# RevA.net
KiCad netlist of a schematic drawn in EAGLE
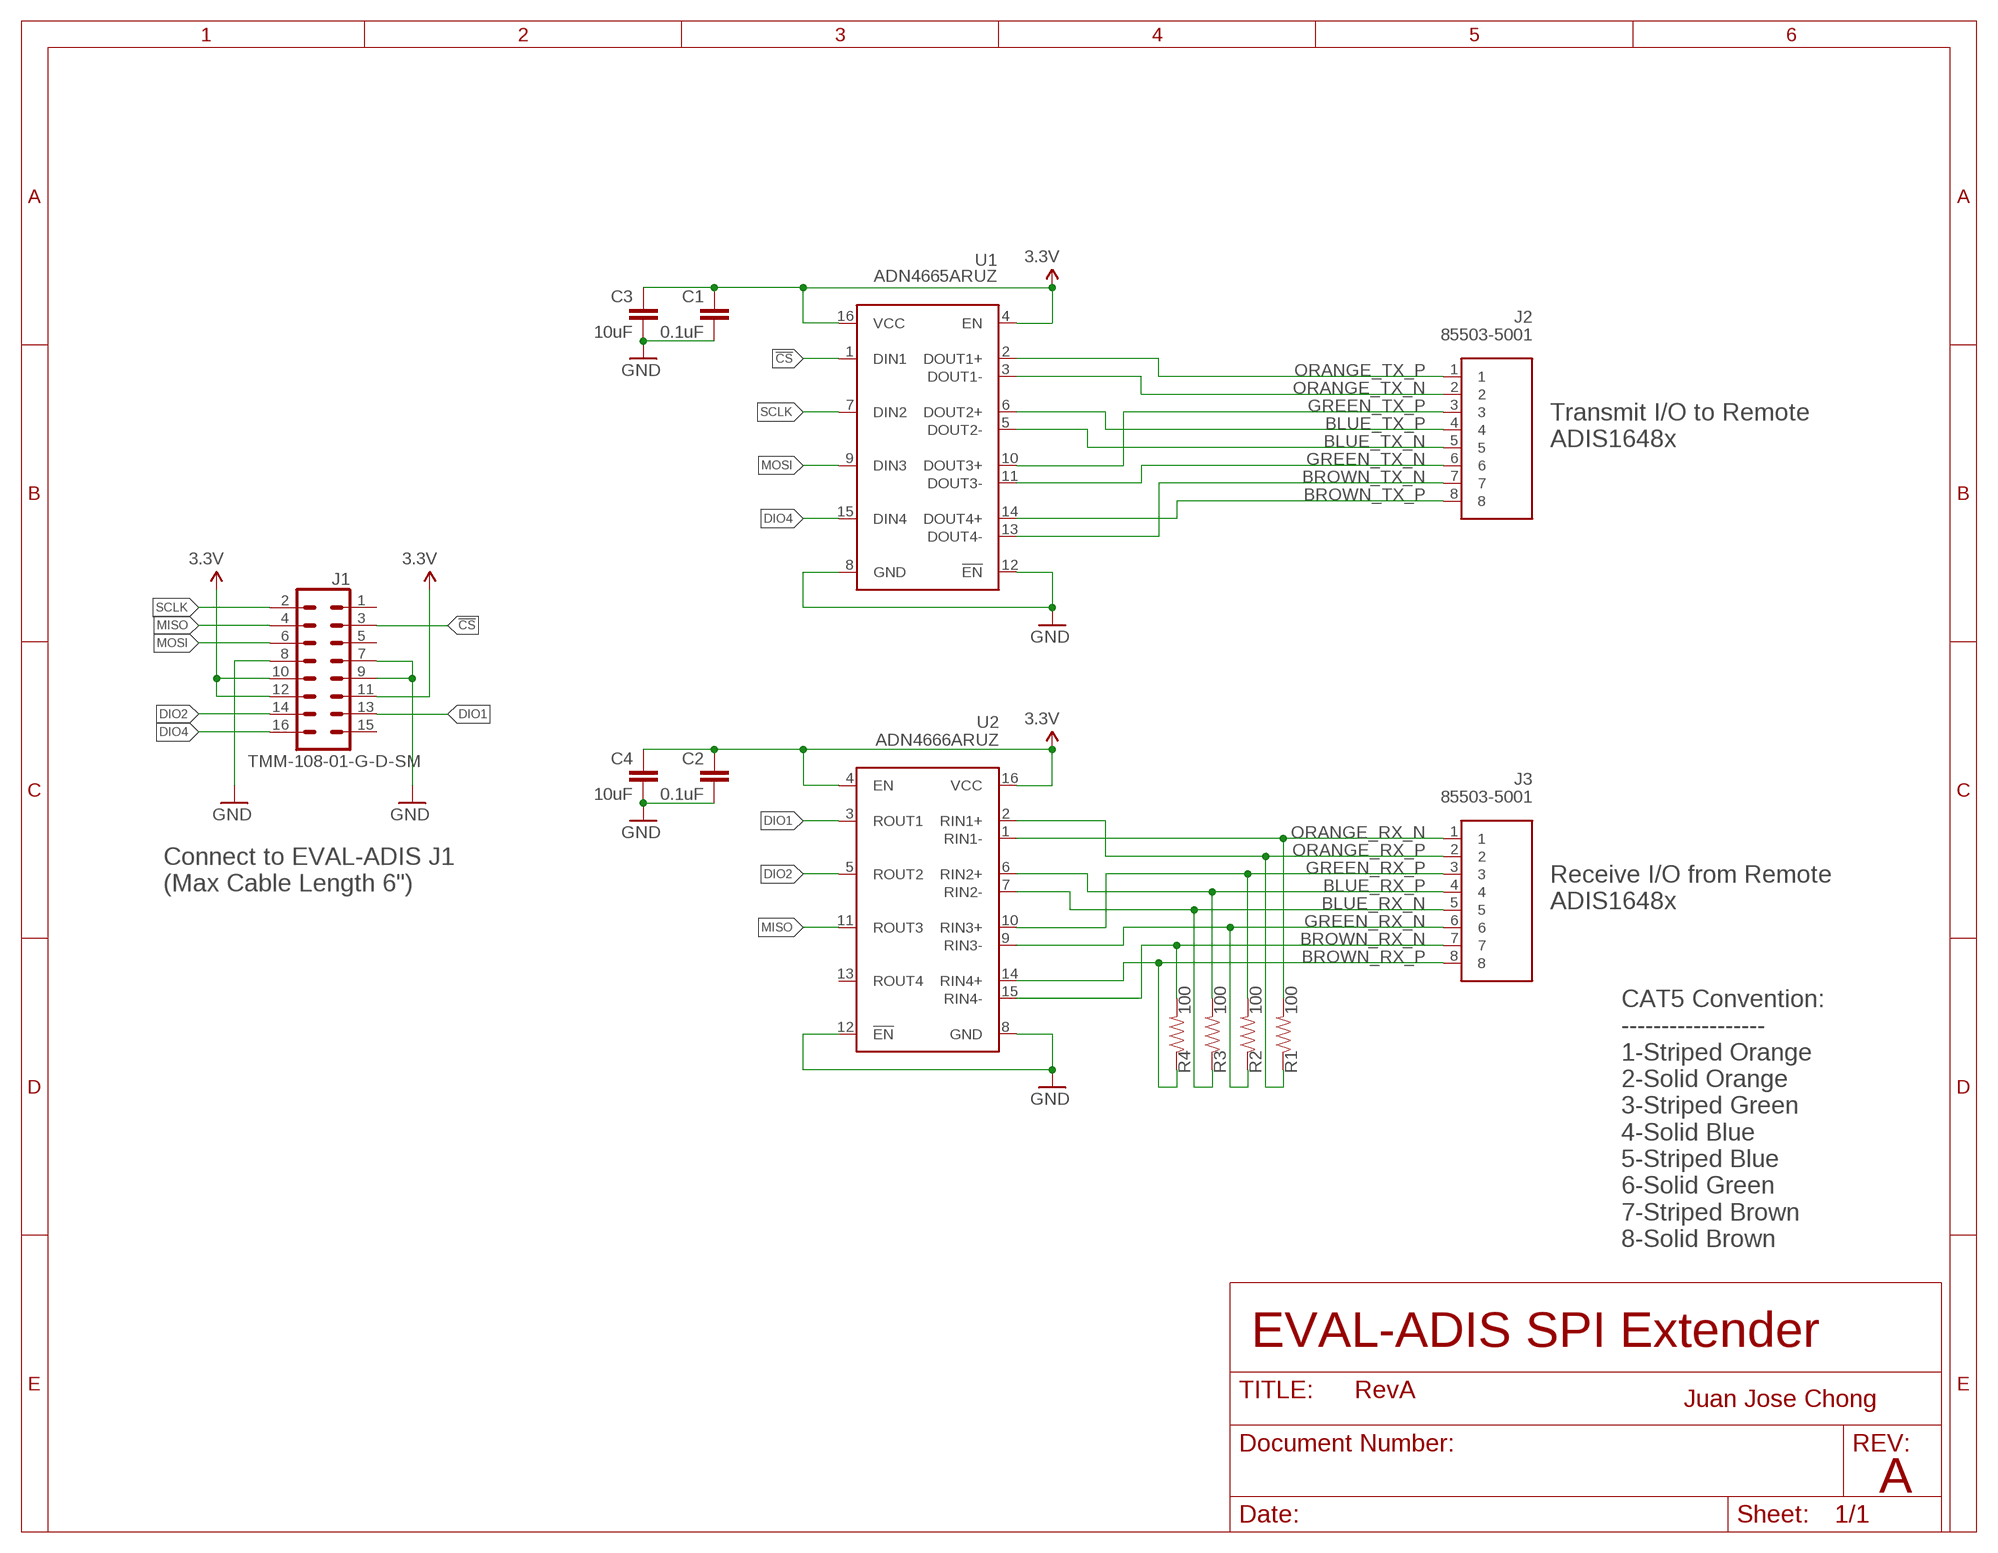
[diagram p0: schematic, sheet 1]

(export (version "E")
  (design (tool "Eeschema 10.0.6"))
  (components
    (comp (ref "C1")
      (value "0.1uF")
      (footprint "eagle-import:0805")
      (fields (field (name "PARTNO") "CL10B104KB8NNNC"))
      (libsource (lib "eagle-import") (part "CAP0805"))
    )
    (comp (ref "C2")
      (value "0.1uF")
      (footprint "eagle-import:0805")
      (fields (field (name "PARTNO") "CL10B104KB8NNNC"))
      (libsource (lib "eagle-import") (part "CAP0805"))
    )
    (comp (ref "C3")
      (value "10uF")
      (footprint "eagle-import:1206")
      (fields (field (name "PARTNO") "F931C106MAA"))
      (libsource (lib "eagle-import") (part "CAP1206"))
    )
    (comp (ref "C4")
      (value "10uF")
      (footprint "eagle-import:1206")
      (fields (field (name "PARTNO") "F931C106MAA"))
      (libsource (lib "eagle-import") (part "CAP1206"))
    )
    (comp (ref "J1")
      (value "TMM-108-01-G-D-SM")
      (footprint "eagle-import:TMM-108-XX-X-D")
      (libsource (lib "eagle-import") (part "TMM-108-XX-X-D"))
    )
    (comp (ref "J2")
      (value "85503-5001")
      (footprint "eagle-import:85503-5001")
      (fields (field (name "PARTNO") "855035001"))
      (libsource (lib "eagle-import") (part "85503-5001"))
    )
    (comp (ref "J3")
      (value "85503-5001")
      (footprint "eagle-import:85503-5001")
      (fields (field (name "PARTNO") "855035001"))
      (libsource (lib "eagle-import") (part "85503-5001"))
    )
    (comp (ref "R1")
      (value "100")
      (footprint "eagle-import:0603-RES")
      (fields (field (name "PARTNO") "ERJ-3EKF1000V"))
      (libsource (lib "eagle-import") (part "RESISTOR0603-RES"))
    )
    (comp (ref "R2")
      (value "100")
      (footprint "eagle-import:0603-RES")
      (fields (field (name "PARTNO") "ERJ-3EKF1000V"))
      (libsource (lib "eagle-import") (part "RESISTOR0603-RES"))
    )
    (comp (ref "R3")
      (value "100")
      (footprint "eagle-import:0603-RES")
      (fields (field (name "PARTNO") "ERJ-3EKF1000V"))
      (libsource (lib "eagle-import") (part "RESISTOR0603-RES"))
    )
    (comp (ref "R4")
      (value "100")
      (footprint "eagle-import:0603-RES")
      (fields (field (name "PARTNO") "ERJ-3EKF1000V"))
      (libsource (lib "eagle-import") (part "RESISTOR0603-RES"))
    )
    (comp (ref "U1")
      (value "ADN4665ARUZ")
      (footprint "eagle-import:TSSOP-16")
      (libsource (lib "eagle-import") (part "ADN4665ARUZ"))
    )
    (comp (ref "U2")
      (value "ADN4666ARUZ")
      (footprint "eagle-import:TSSOP-16")
      (libsource (lib "eagle-import") (part "ADN4666ARUZ"))
    )
  )
  (nets
    (net (code "1") (name "/BLUE_RX_N") (class "Default")
      (node (ref "J3") (pin "5") (pinfunction "5_5") (pintype "bidirectional"))
      (node (ref "R3") (pin "1") (pinfunction "1_1") (pintype "passive"))
      (node (ref "U2") (pin "7") (pinfunction "RIN2-_7") (pintype "bidirectional"))
    )
    (net (code "2") (name "/BLUE_RX_P") (class "Default")
      (node (ref "J3") (pin "4") (pinfunction "4_4") (pintype "bidirectional"))
      (node (ref "R3") (pin "2") (pinfunction "2_2") (pintype "passive"))
      (node (ref "U2") (pin "6") (pinfunction "RIN2+_6") (pintype "bidirectional"))
    )
    (net (code "3") (name "/BLUE_TX_N") (class "Default")
      (node (ref "J2") (pin "5") (pinfunction "5_5") (pintype "bidirectional"))
      (node (ref "U1") (pin "5") (pinfunction "DOUT2-_5") (pintype "bidirectional"))
    )
    (net (code "4") (name "/BLUE_TX_P") (class "Default")
      (node (ref "J2") (pin "4") (pinfunction "4_4") (pintype "bidirectional"))
      (node (ref "U1") (pin "6") (pinfunction "DOUT2+_6") (pintype "bidirectional"))
    )
    (net (code "5") (name "/BROWN_RX_N") (class "Default")
      (node (ref "J3") (pin "7") (pinfunction "7_7") (pintype "bidirectional"))
      (node (ref "R4") (pin "2") (pinfunction "2_2") (pintype "passive"))
      (node (ref "U2") (pin "15") (pinfunction "RIN4-_15") (pintype "bidirectional"))
    )
    (net (code "6") (name "/BROWN_RX_P") (class "Default")
      (node (ref "J3") (pin "8") (pinfunction "8_8") (pintype "bidirectional"))
      (node (ref "R4") (pin "1") (pinfunction "1_1") (pintype "passive"))
      (node (ref "U2") (pin "14") (pinfunction "RIN4+_14") (pintype "bidirectional"))
    )
    (net (code "7") (name "/BROWN_TX_N") (class "Default")
      (node (ref "J2") (pin "7") (pinfunction "7_7") (pintype "bidirectional"))
      (node (ref "U1") (pin "13") (pinfunction "DOUT4-_13") (pintype "bidirectional"))
    )
    (net (code "8") (name "/BROWN_TX_P") (class "Default")
      (node (ref "J2") (pin "8") (pinfunction "8_8") (pintype "bidirectional"))
      (node (ref "U1") (pin "14") (pinfunction "DOUT4+_14") (pintype "bidirectional"))
    )
    (net (code "9") (name "/GREEN_RX_N") (class "Default")
      (node (ref "J3") (pin "6") (pinfunction "6_6") (pintype "bidirectional"))
      (node (ref "R2") (pin "1") (pinfunction "1_1") (pintype "passive"))
      (node (ref "U2") (pin "9") (pinfunction "RIN3-_9") (pintype "bidirectional"))
    )
    (net (code "10") (name "/GREEN_RX_P") (class "Default")
      (node (ref "J3") (pin "3") (pinfunction "3_3") (pintype "bidirectional"))
      (node (ref "R2") (pin "2") (pinfunction "2_2") (pintype "passive"))
      (node (ref "U2") (pin "10") (pinfunction "RIN3+_10") (pintype "bidirectional"))
    )
    (net (code "11") (name "/GREEN_TX_N") (class "Default")
      (node (ref "J2") (pin "6") (pinfunction "6_6") (pintype "bidirectional"))
      (node (ref "U1") (pin "11") (pinfunction "DOUT3-_11") (pintype "bidirectional"))
    )
    (net (code "12") (name "/GREEN_TX_P") (class "Default")
      (node (ref "J2") (pin "3") (pinfunction "3_3") (pintype "bidirectional"))
      (node (ref "U1") (pin "10") (pinfunction "DOUT3+_10") (pintype "bidirectional"))
    )
    (net (code "13") (name "/ORANGE_RX_N") (class "Default")
      (node (ref "J3") (pin "1") (pinfunction "1_1") (pintype "bidirectional"))
      (node (ref "R1") (pin "2") (pinfunction "2_2") (pintype "passive"))
      (node (ref "U2") (pin "1") (pinfunction "RIN1-_1") (pintype "bidirectional"))
    )
    (net (code "14") (name "/ORANGE_RX_P") (class "Default")
      (node (ref "J3") (pin "2") (pinfunction "2_2") (pintype "bidirectional"))
      (node (ref "R1") (pin "1") (pinfunction "1_1") (pintype "passive"))
      (node (ref "U2") (pin "2") (pinfunction "RIN1+_2") (pintype "bidirectional"))
    )
    (net (code "15") (name "/ORANGE_TX_N") (class "Default")
      (node (ref "J2") (pin "2") (pinfunction "2_2") (pintype "bidirectional"))
      (node (ref "U1") (pin "3") (pinfunction "DOUT1-_3") (pintype "bidirectional"))
    )
    (net (code "16") (name "/ORANGE_TX_P") (class "Default")
      (node (ref "J2") (pin "1") (pinfunction "1_1") (pintype "bidirectional"))
      (node (ref "U1") (pin "2") (pinfunction "DOUT1+_2") (pintype "bidirectional"))
    )
    (net (code "17") (name "/~{CS}") (class "Default")
      (node (ref "J1") (pin "3") (pinfunction "3_3") (pintype "passive"))
      (node (ref "U1") (pin "1") (pinfunction "DIN1_1") (pintype "bidirectional"))
    )
    (net (code "18") (name "3.3V") (class "Default")
      (node (ref "C1") (pin "1") (pinfunction "1_1") (pintype "passive"))
      (node (ref "C2") (pin "1") (pinfunction "1_1") (pintype "passive"))
      (node (ref "C3") (pin "1") (pinfunction "1_1") (pintype "passive"))
      (node (ref "C4") (pin "1") (pinfunction "1_1") (pintype "passive"))
      (node (ref "J1") (pin "10") (pinfunction "10_10") (pintype "passive"))
      (node (ref "J1") (pin "11") (pinfunction "11_11") (pintype "passive"))
      (node (ref "J1") (pin "12") (pinfunction "12_12") (pintype "passive"))
      (node (ref "U1") (pin "16") (pinfunction "VCC_16") (pintype "bidirectional"))
      (node (ref "U1") (pin "4") (pinfunction "EN_4") (pintype "bidirectional"))
      (node (ref "U2") (pin "16") (pinfunction "VCC_16") (pintype "bidirectional"))
      (node (ref "U2") (pin "4") (pinfunction "EN_4") (pintype "bidirectional"))
    )
    (net (code "19") (name "DIO1") (class "Default")
      (node (ref "J1") (pin "13") (pinfunction "13_13") (pintype "passive"))
      (node (ref "U2") (pin "3") (pinfunction "ROUT1_3") (pintype "bidirectional"))
    )
    (net (code "20") (name "DIO2") (class "Default")
      (node (ref "J1") (pin "14") (pinfunction "14_14") (pintype "passive"))
      (node (ref "U2") (pin "5") (pinfunction "ROUT2_5") (pintype "bidirectional"))
    )
    (net (code "21") (name "DIO4") (class "Default")
      (node (ref "J1") (pin "16") (pinfunction "16_16") (pintype "passive"))
      (node (ref "U1") (pin "15") (pinfunction "DIN4_15") (pintype "bidirectional"))
    )
    (net (code "22") (name "GND") (class "Default")
      (node (ref "C1") (pin "2") (pinfunction "2_2") (pintype "passive"))
      (node (ref "C2") (pin "2") (pinfunction "2_2") (pintype "passive"))
      (node (ref "C3") (pin "2") (pinfunction "2_2") (pintype "passive"))
      (node (ref "C4") (pin "2") (pinfunction "2_2") (pintype "passive"))
      (node (ref "J1") (pin "7") (pinfunction "7_7") (pintype "passive"))
      (node (ref "J1") (pin "8") (pinfunction "8_8") (pintype "passive"))
      (node (ref "J1") (pin "9") (pinfunction "9_9") (pintype "passive"))
      (node (ref "U1") (pin "12") (pinfunction "~{EN}_12") (pintype "bidirectional"))
      (node (ref "U1") (pin "8") (pinfunction "GND_8") (pintype "bidirectional"))
      (node (ref "U2") (pin "12") (pinfunction "~{EN}_12") (pintype "bidirectional"))
      (node (ref "U2") (pin "8") (pinfunction "GND_8") (pintype "bidirectional"))
    )
    (net (code "23") (name "MISO") (class "Default")
      (node (ref "J1") (pin "4") (pinfunction "4_4") (pintype "passive"))
      (node (ref "U2") (pin "11") (pinfunction "ROUT3_11") (pintype "bidirectional"))
    )
    (net (code "24") (name "MOSI") (class "Default")
      (node (ref "J1") (pin "6") (pinfunction "6_6") (pintype "passive"))
      (node (ref "U1") (pin "9") (pinfunction "DIN3_9") (pintype "bidirectional"))
    )
    (net (code "25") (name "SCLK") (class "Default")
      (node (ref "J1") (pin "2") (pinfunction "2_2") (pintype "passive"))
      (node (ref "U1") (pin "7") (pinfunction "DIN2_7") (pintype "bidirectional"))
    )
    (net (code "26") (name "unconnected-(J1-Pad1)") (class "Default")
      (node (ref "J1") (pin "1") (pinfunction "1_1") (pintype "passive"))
    )
    (net (code "27") (name "unconnected-(J1-Pad5)") (class "Default")
      (node (ref "J1") (pin "5") (pinfunction "5_5") (pintype "passive"))
    )
    (net (code "28") (name "unconnected-(J1-Pad15)") (class "Default")
      (node (ref "J1") (pin "15") (pinfunction "15_15") (pintype "passive"))
    )
    (net (code "29") (name "unconnected-(U2-ROUT4-Pad13)") (class "Default")
      (node (ref "U2") (pin "13") (pinfunction "ROUT4_13") (pintype "bidirectional"))
    )
  )
)
